# top_tnb_mns_control.net
KiCad netlist of a schematic drawn in Altium Designer
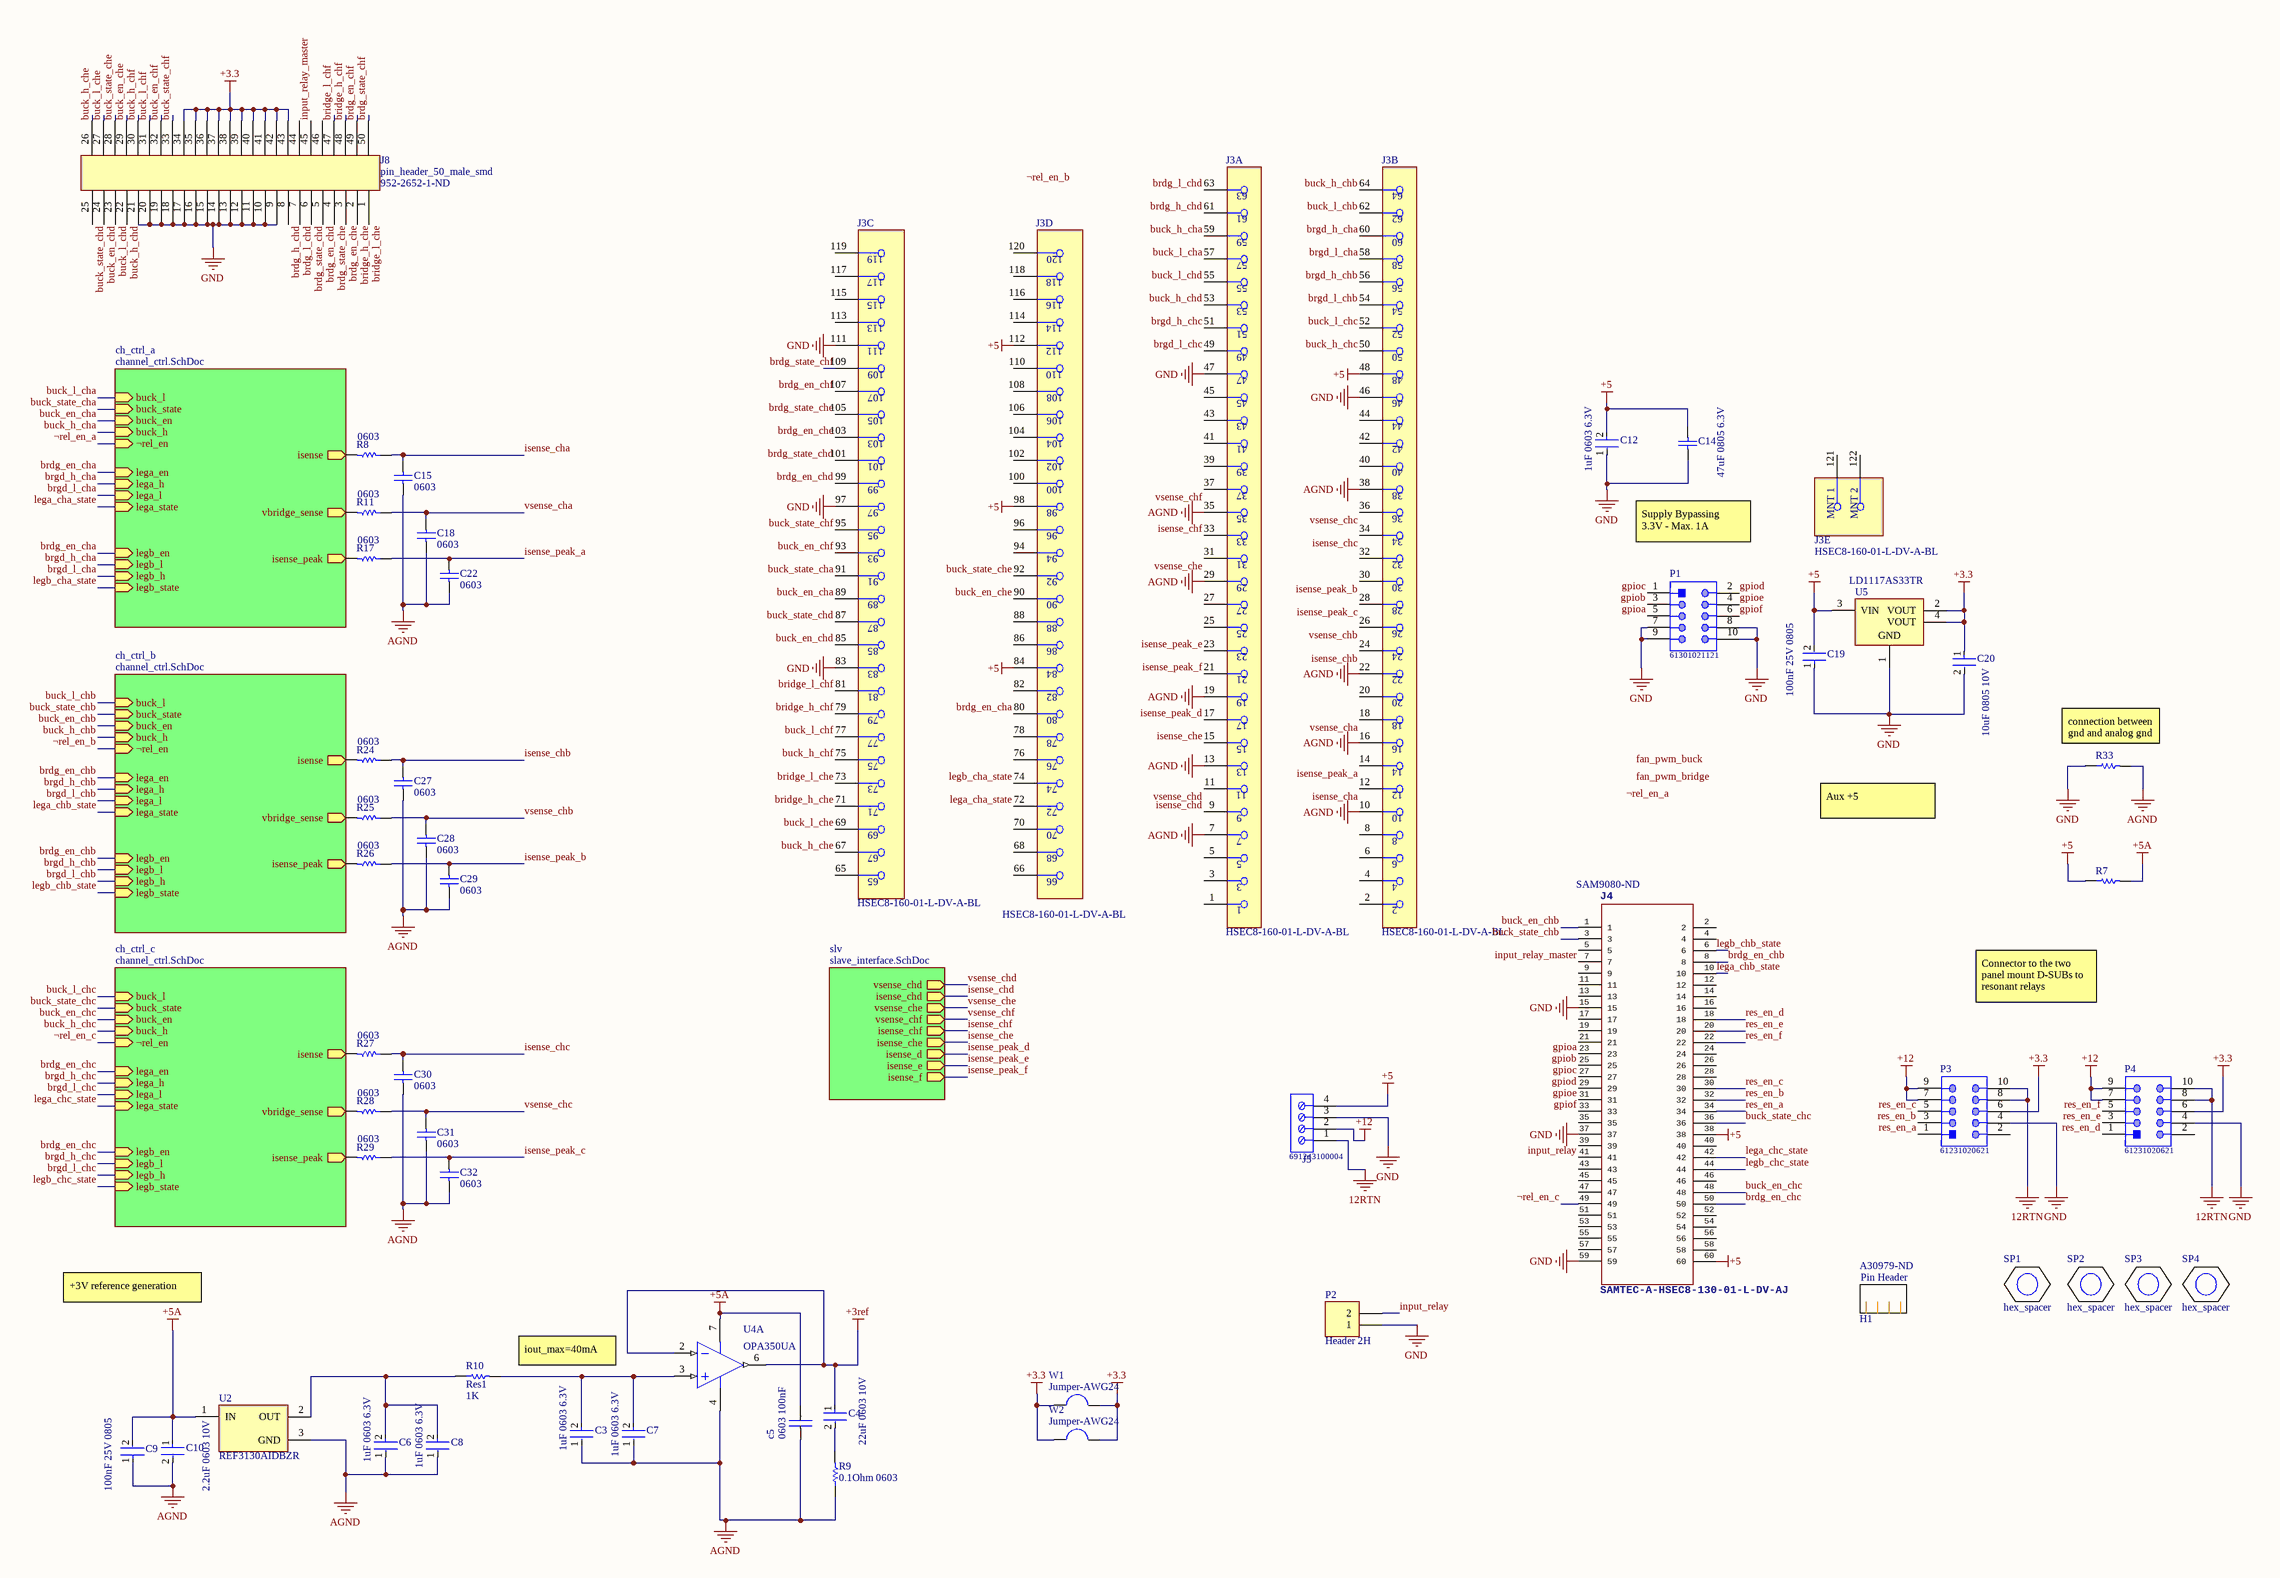
[diagram p0: top_tnb_mns_control.SchDoc]

(export (version "E")
  (design (tool "Eeschema 10.0.6"))
  (components
    (comp (ref "C3")
      (value "1uF 0603 6.3V")
      (footprint "FP-GRM188-0_1-MFG")
      (description "CAP CER 1UF 6.3V X5R 0603\r\nGRM188R60J105KA01D")
      (fields (field (name "TOLERANCE") "10%") (field (name "VOLTAGE") "6.3V"))
      (libsource (lib "Altium Content Vault") (part "236180d848d6139a670b325ea6854c9"))
    )
    (comp (ref "C4")
      (value "22uF 0603 10V")
      (footprint "FP-GRM188-0_2-IPC_C")
      (fields (field (name "TOLERANCE") "20%"))
      (libsource (lib "Altium Content Vault") (part "11868f565c42a9108669ba33697ecf6"))
    )
    (comp (ref "c5")
      (value "0603 100nF")
      (footprint "CAP 0603_1608")
      (libsource (lib "coil_driver_lib") (part "cap_smd"))
    )
    (comp (ref "C6")
      (value "1uF 0603 6.3V")
      (footprint "FP-GRM188-0_1-MFG")
      (description "CAP CER 1UF 6.3V X5R 0603\r\nGRM188R60J105KA01D")
      (fields (field (name "TOLERANCE") "10%") (field (name "VOLTAGE") "6.3V"))
      (libsource (lib "Altium Content Vault") (part "236180d848d6139a670b325ea6854c9"))
    )
    (comp (ref "C7")
      (value "1uF 0603 6.3V")
      (footprint "FP-GRM188-0_1-MFG")
      (description "CAP CER 1UF 6.3V X5R 0603\r\nGRM188R60J105KA01D")
      (fields (field (name "TOLERANCE") "10%") (field (name "VOLTAGE") "6.3V"))
      (libsource (lib "Altium Content Vault") (part "236180d848d6139a670b325ea6854c9"))
    )
    (comp (ref "C8")
      (value "1uF 0603 6.3V")
      (footprint "FP-GRM188-0_1-MFG")
      (description "CAP CER 1UF 6.3V X5R 0603\r\nGRM188R60J105KA01D")
      (fields (field (name "TOLERANCE") "10%") (field (name "VOLTAGE") "6.3V"))
      (libsource (lib "Altium Content Vault") (part "236180d848d6139a670b325ea6854c9"))
    )
    (comp (ref "C9")
      (value "100nF 25V 0805")
      (footprint "FP-CC0805-0_85-MFG")
      (description "CAP CER 0.1UF 25V X7R 0805")
      (fields (field (name "MANUFACTURER PART NUMBER") "CC0805KRX7R8BB104") (field (name "TOLERANCE") "0.1"))
      (libsource (lib "Altium Content Vault") (part "11868f565c42a9108669ba33697ecf6"))
    )
    (comp (ref "C10")
      (value "2.2uF 0603 10V")
      (footprint "FP-GRM188-0_1-e0_2_0_5-MFG")
      (fields (field (name "VOLTAGE") "10V") (field (name "TOLERANCE") "10%"))
      (libsource (lib "Altium Content Vault") (part "11868f565c42a9108669ba33697ecf6"))
    )
    (comp (ref "C12")
      (value "1uF 0603 6.3V")
      (footprint "FP-GRM188-0_1-MFG")
      (description "CAP CER 1UF 6.3V X5R 0603\r\nGRM188R60J105KA01D")
      (fields (field (name "TOLERANCE") "10%") (field (name "VOLTAGE") "6.3V"))
      (libsource (lib "Altium Content Vault") (part "236180d848d6139a670b325ea6854c9"))
    )
    (comp (ref "C14")
      (value "47uF 0805 6.3V")
      (footprint "CAPC2014X150X70LL20")
      (description "TACR476M006XTA")
      (fields (field (name "MANUFACTURER") "AVX Interconnect / Elco"))
      (libsource (lib "Altium Content Vault") (part "CAP"))
    )
    (comp (ref "C15")
      (value "0603")
      (footprint "CAP 0603_1608")
      (description "Capacitor")
      (fields (field (name "PUBLISHER") "Altium Limited"))
      (libsource (lib "Miscellaneous Devices") (part "Cap"))
    )
    (comp (ref "C18")
      (value "0603")
      (footprint "CAP 0603_1608")
      (description "Capacitor")
      (fields (field (name "PUBLISHER") "Altium Limited"))
      (libsource (lib "Miscellaneous Devices") (part "Cap"))
    )
    (comp (ref "C19")
      (value "100nF 25V 0805")
      (footprint "FP-CC0805-0_85-MFG")
      (description "CAP CER 0.1UF 25V X7R 0805")
      (fields (field (name "MANUFACTURER PART NUMBER") "CC0805KRX7R8BB104") (field (name "TOLERANCE") "0.1"))
      (libsource (lib "Altium Content Vault") (part "11868f565c42a9108669ba33697ecf6"))
    )
    (comp (ref "C20")
      (value "10uF 0805 10V")
      (footprint "FP-C0805C-DG-MFG")
      (description "CAP CER 10UF 10V X5R 0805\r\nC0805C106K8PACTU")
      (fields (field (name "TOLERANCE") "10%") (field (name "MANUFACTURER PART NUMBER") "C0805C106K8PACTU"))
      (libsource (lib "Altium Content Vault") (part "11868f565c42a9108669ba33697ecf6"))
    )
    (comp (ref "C22")
      (value "0603")
      (footprint "CAP 0603_1608")
      (description "Capacitor")
      (fields (field (name "PUBLISHER") "Altium Limited"))
      (libsource (lib "Miscellaneous Devices") (part "Cap"))
    )
    (comp (ref "C27")
      (value "0603")
      (footprint "CAP 0603_1608")
      (description "Capacitor")
      (fields (field (name "PUBLISHER") "Altium Limited"))
      (libsource (lib "Miscellaneous Devices") (part "Cap"))
    )
    (comp (ref "C28")
      (value "0603")
      (footprint "CAP 0603_1608")
      (description "Capacitor")
      (fields (field (name "PUBLISHER") "Altium Limited"))
      (libsource (lib "Miscellaneous Devices") (part "Cap"))
    )
    (comp (ref "C29")
      (value "0603")
      (footprint "CAP 0603_1608")
      (description "Capacitor")
      (fields (field (name "PUBLISHER") "Altium Limited"))
      (libsource (lib "Miscellaneous Devices") (part "Cap"))
    )
    (comp (ref "C30")
      (value "0603")
      (footprint "CAP 0603_1608")
      (description "Capacitor")
      (fields (field (name "PUBLISHER") "Altium Limited"))
      (libsource (lib "Miscellaneous Devices") (part "Cap"))
    )
    (comp (ref "C31")
      (value "0603")
      (footprint "CAP 0603_1608")
      (description "Capacitor")
      (fields (field (name "PUBLISHER") "Altium Limited"))
      (libsource (lib "Miscellaneous Devices") (part "Cap"))
    )
    (comp (ref "C32")
      (value "0603")
      (footprint "CAP 0603_1608")
      (description "Capacitor")
      (fields (field (name "PUBLISHER") "Altium Limited"))
      (libsource (lib "Miscellaneous Devices") (part "Cap"))
    )
    (comp (ref "H1")
      (value "Generic Pin  Header")
      (description "Assign Supplier Link Manually")
      (fields (field (name "SUPPLIER PART NUMBER 1") "A30979-ND"))
      (libsource (lib "coil_driver_lib") (part "generic_pin_header"))
    )
    (comp (ref "J3")
      (value "HSEC8-160-01-L-DV-A-BL")
      (footprint "FP-HSEC8-160-01-L-DV-A-BL-MFG")
      (description "CONN EDGE DUAL FMALE 120P 0.031")
      (libsource (lib "Altium Content Vault") (part "8744de41cb8216e3d623a7aa1f0e41a"))
    )
    (comp (ref "J4")
      (value "SAMTEC-A-HSEC8-130-01-L-DV-AJ")
      (footprint "SAMTEC-A-HSEC-120")
      (fields (field (name "SUPPLIER PART NUMBER 1") "SAM9080-ND"))
      (libsource (lib "SAMTEC-A-HSEC8-130-01-L-DV-A") (part "SAMTEC-A-HSEC8-130-01-L-DV-AJ"))
    )
    (comp (ref "J5")
      (value "691243100004")
      (footprint "691243100004")
      (description "Serie 2431- 3.50 mm Vertical Entry with Rising Cage Clamp WR-TBL, 4 pin")
      (fields (field (name "MANUFACTURER") "Wurth Elektronik") (field (name "PUBLISHER") "WurthElektronik"))
      (libsource (lib "Altium Content Vault") (part "WE-CN-1P-F-TB4"))
    )
    (comp (ref "J8")
      (value "pin_header_50_male_smd")
      (footprint "pin_connector_50_m_1.27_smd")
      (description "Mating Product : 952-2565-ND")
      (fields (field (name "SUPPLIER PART NUMBER 1") "952-2652-1-ND"))
      (libsource (lib "coil_driver_lib") (part "pin_header_50_male_smd"))
    )
    (comp (ref "P1")
      (value "61301021121")
      (footprint "61301021121")
      (description "THT Vertical Pin Header WR-PHD, Pitch 2.54 mm, Dual Row, 10 pins")
      (fields (field (name "MANUFACTURER") "Wurth Elektronik") (field (name "PUBLISHER") "WurthElektronik"))
      (libsource (lib "Altium Content Vault") (part "WE-CN-2P-M-R10"))
    )
    (comp (ref "P2")
      (value "Header 2H")
      (footprint "HEADER_1_2_f")
      (description "Header, 2-Pin, Right Angle")
      (fields (field (name "PUBLISHER") "Altium Limited"))
      (libsource (lib "Miscellaneous Connectors") (part "Header 2H"))
    )
    (comp (ref "P3")
      (value "61231020621")
      (footprint "61231020621")
      (description "Male Box Header WR-BHD, SMT, Vertical, pitch 2.54 mm, 10 pins")
      (fields (field (name "MANUFACTURER") "Wurth Elektronik") (field (name "PUBLISHER") "WurthElektronik"))
      (libsource (lib "") (part "WE-CN-2P-M-R10_1"))
    )
    (comp (ref "P4")
      (value "61231020621")
      (footprint "61231020621")
      (description "Male Box Header WR-BHD, SMT, Vertical, pitch 2.54 mm, 10 pins")
      (fields (field (name "MANUFACTURER") "Wurth Elektronik") (field (name "PUBLISHER") "WurthElektronik"))
      (libsource (lib "") (part "WE-CN-2P-M-R10_1"))
    )
    (comp (ref "R7")
      (value "0")
      (footprint "RES 0805_2012")
      (description "Resistor")
      (fields (field (name "PUBLISHER") "Altium Limited"))
      (libsource (lib "Miscellaneous Devices") (part "Res1"))
    )
    (comp (ref "R8")
      (value "0603")
      (footprint "RES 0603_1608")
      (description "Resistor")
      (fields (field (name "PUBLISHER") "Altium Limited"))
      (libsource (lib "Miscellaneous Devices") (part "Res1"))
    )
    (comp (ref "R9")
      (value "0.1Ohm 0603")
      (footprint "RESC1508X46X38NL25T25")
      (description "WSL0603R1000FEA")
      (fields (field (name "MANUFACTURER") "Vishay Dale"))
      (libsource (lib "Altium Content Vault") (part "RES"))
    )
    (comp (ref "R10")
      (value "Res1")
      (footprint "RES 0603_1608")
      (description "Resistor")
      (fields (field (name "ALTIUM_VALUE") "1K") (field (name "PUBLISHER") "Altium Limited"))
      (libsource (lib "Miscellaneous Devices") (part "Res1"))
    )
    (comp (ref "R11")
      (value "0603")
      (footprint "RES 0603_1608")
      (description "Resistor")
      (fields (field (name "PUBLISHER") "Altium Limited"))
      (libsource (lib "Miscellaneous Devices") (part "Res1"))
    )
    (comp (ref "R17")
      (value "0603")
      (footprint "RES 0603_1608")
      (description "Resistor")
      (fields (field (name "PUBLISHER") "Altium Limited"))
      (libsource (lib "Miscellaneous Devices") (part "Res1"))
    )
    (comp (ref "R24")
      (value "0603")
      (footprint "RES 0603_1608")
      (description "Resistor")
      (fields (field (name "PUBLISHER") "Altium Limited"))
      (libsource (lib "Miscellaneous Devices") (part "Res1"))
    )
    (comp (ref "R25")
      (value "0603")
      (footprint "RES 0603_1608")
      (description "Resistor")
      (fields (field (name "PUBLISHER") "Altium Limited"))
      (libsource (lib "Miscellaneous Devices") (part "Res1"))
    )
    (comp (ref "R26")
      (value "0603")
      (footprint "RES 0603_1608")
      (description "Resistor")
      (fields (field (name "PUBLISHER") "Altium Limited"))
      (libsource (lib "Miscellaneous Devices") (part "Res1"))
    )
    (comp (ref "R27")
      (value "0603")
      (footprint "RES 0603_1608")
      (description "Resistor")
      (fields (field (name "PUBLISHER") "Altium Limited"))
      (libsource (lib "Miscellaneous Devices") (part "Res1"))
    )
    (comp (ref "R28")
      (value "0603")
      (footprint "RES 0603_1608")
      (description "Resistor")
      (fields (field (name "PUBLISHER") "Altium Limited"))
      (libsource (lib "Miscellaneous Devices") (part "Res1"))
    )
    (comp (ref "R29")
      (value "0603")
      (footprint "RES 0603_1608")
      (description "Resistor")
      (fields (field (name "PUBLISHER") "Altium Limited"))
      (libsource (lib "Miscellaneous Devices") (part "Res1"))
    )
    (comp (ref "R33")
      (value "0")
      (footprint "RES 0805_2012")
      (description "Resistor")
      (fields (field (name "PUBLISHER") "Altium Limited"))
      (libsource (lib "Miscellaneous Devices") (part "Res1"))
    )
    (comp (ref "SP1")
      (value "hex_spacer")
      (footprint "HEX_SPACER_8MM_35MM")
      (libsource (lib "coil_driver_lib") (part "hex_spacer"))
    )
    (comp (ref "SP2")
      (value "hex_spacer")
      (footprint "HEX_SPACER_8MM_35MM")
      (libsource (lib "coil_driver_lib") (part "hex_spacer"))
    )
    (comp (ref "SP3")
      (value "hex_spacer")
      (footprint "HEX_SPACER_8MM_35MM")
      (libsource (lib "coil_driver_lib") (part "hex_spacer"))
    )
    (comp (ref "SP4")
      (value "hex_spacer")
      (footprint "HEX_SPACER_8MM_35MM")
      (libsource (lib "coil_driver_lib") (part "hex_spacer"))
    )
    (comp (ref "U2")
      (value "REF3130AIDBZR")
      (footprint "DBZ0003A_N")
      (fields (field (name "MANUFACTURER") "Texas Instruments"))
      (libsource (lib "Altium Content Vault") (part "TI-REF3130DBZ3"))
    )
    (comp (ref "U4")
      (value "OPA350UA")
      (footprint "D0008A_M")
      (fields (field (name "MANUFACTURER") "Texas Instruments"))
      (libsource (lib "Altium Content Vault") (part "TI-OPA-8_1"))
    )
    (comp (ref "U5")
      (value "LD1117AS33TR")
      (footprint "SOT-223_M")
      (description "1A, Low Drop Positive Voltage Regulator, 3.3V, 4-Pin SOT-223, Tape and Reel")
      (libsource (lib "Altium Content Vault") (part "PM-REG-LD1117-SOT4"))
    )
    (comp (ref "W1")
      (value "wire_jumper")
      (footprint "wire_jumper")
      (libsource (lib "coil_driver_lib") (part "wire_jumper"))
    )
    (comp (ref "W2")
      (value "wire_jumper")
      (footprint "wire_jumper")
      (libsource (lib "coil_driver_lib") (part "wire_jumper"))
    )
  )
  (nets
    (net (code "1") (name "+3.3") (class "Default")
      (node (ref "C20") (pin "1") (pinfunction "1_1") (pintype "passive"))
      (node (ref "J8") (pin "34") (pintype "passive"))
      (node (ref "J8") (pin "35") (pintype "passive"))
      (node (ref "J8") (pin "36") (pintype "passive"))
      (node (ref "J8") (pin "37") (pintype "passive"))
      (node (ref "J8") (pin "38") (pintype "passive"))
      (node (ref "J8") (pin "39") (pintype "passive"))
      (node (ref "J8") (pin "40") (pintype "passive"))
      (node (ref "J8") (pin "41") (pintype "passive"))
      (node (ref "J8") (pin "42") (pintype "passive"))
      (node (ref "J8") (pin "43") (pintype "passive"))
      (node (ref "P3") (pin "6") (pinfunction "6_6") (pintype "passive"))
      (node (ref "P4") (pin "6") (pinfunction "6_6") (pintype "passive"))
      (node (ref "U5") (pin "2") (pinfunction "VOUT_2") (pintype "power_in"))
      (node (ref "U5") (pin "4") (pinfunction "VOUT_4") (pintype "power_in"))
      (node (ref "W1") (pin "1") (pinfunction "1_1") (pintype "passive"))
      (node (ref "W1") (pin "2") (pinfunction "2_2") (pintype "passive"))
      (node (ref "W2") (pin "1") (pinfunction "1_1") (pintype "passive"))
      (node (ref "W2") (pin "2") (pinfunction "2_2") (pintype "passive"))
    )
    (net (code "2") (name "+3ref") (class "Default")
      (node (ref "C4") (pin "1") (pinfunction "1_1") (pintype "passive"))
      (node (ref "U4") (pin "2") (pinfunction "IN-_2") (pintype "input"))
      (node (ref "U4") (pin "6") (pinfunction "OUT_6") (pintype "output"))
    )
    (net (code "3") (name "+5") (class "Default")
      (node (ref "C12") (pin "2") (pinfunction "2_2") (pintype "passive"))
      (node (ref "C14") (pin "2") (pinfunction "2_2") (pintype "passive"))
      (node (ref "C19") (pin "2") (pinfunction "2_2") (pintype "passive"))
      (node (ref "J3") (pin "112") (pinfunction "112_112") (pintype "passive"))
      (node (ref "J3") (pin "48") (pinfunction "48_48") (pintype "passive"))
      (node (ref "J3") (pin "84") (pinfunction "84_84") (pintype "passive"))
      (node (ref "J3") (pin "98") (pinfunction "98_98") (pintype "passive"))
      (node (ref "J4") (pin "38") (pinfunction "38_38") (pintype "passive"))
      (node (ref "J4") (pin "60") (pinfunction "60_60") (pintype "passive"))
      (node (ref "J5") (pin "4") (pinfunction "4_4") (pintype "passive"))
      (node (ref "R7") (pin "1") (pinfunction "1_1") (pintype "passive"))
      (node (ref "U5") (pin "3") (pinfunction "VIN_3") (pintype "power_in"))
    )
    (net (code "4") (name "+5A") (class "Default")
      (node (ref "C10") (pin "1") (pinfunction "1_1") (pintype "passive"))
      (node (ref "C9") (pin "2") (pinfunction "2_2") (pintype "passive"))
      (node (ref "R7") (pin "2") (pinfunction "2_2") (pintype "passive"))
      (node (ref "U2") (pin "1") (pinfunction "IN_1") (pintype "power_in"))
      (node (ref "U4") (pin "7") (pinfunction "V+_7") (pintype "power_in"))
      (node (ref "c5") (pin "1") (pinfunction "1_1") (pintype "passive"))
    )
    (net (code "5") (name "+12") (class "Default")
      (node (ref "J5") (pin "2") (pinfunction "2_2") (pintype "passive"))
      (node (ref "P3") (pin "7") (pinfunction "7_7") (pintype "passive"))
      (node (ref "P3") (pin "9") (pinfunction "9_9") (pintype "passive"))
      (node (ref "P4") (pin "7") (pinfunction "7_7") (pintype "passive"))
      (node (ref "P4") (pin "9") (pinfunction "9_9") (pintype "passive"))
    )
    (net (code "6") (name "/brdg_en_cha") (class "Default")
      (node (ref "J3") (pin "80") (pinfunction "80_80") (pintype "passive"))
    )
    (net (code "7") (name "/brdg_en_chb") (class "Default")
      (node (ref "J4") (pin "8") (pinfunction "8_8") (pintype "passive"))
    )
    (net (code "8") (name "/brdg_en_chc") (class "Default")
      (node (ref "J4") (pin "50") (pinfunction "50_50") (pintype "passive"))
    )
    (net (code "9") (name "/brdg_en_chd") (class "Default")
      (node (ref "J3") (pin "99") (pinfunction "99_99") (pintype "passive"))
      (node (ref "J8") (pin "5") (pintype "passive"))
    )
    (net (code "10") (name "/brdg_en_che") (class "Default")
      (node (ref "J3") (pin "103") (pinfunction "103_103") (pintype "passive"))
      (node (ref "J8") (pin "3") (pintype "passive"))
    )
    (net (code "11") (name "/brdg_en_chf") (class "Default")
      (node (ref "J3") (pin "107") (pinfunction "107_107") (pintype "passive"))
      (node (ref "J8") (pin "49") (pintype "passive"))
    )
    (net (code "12") (name "/brdg_h_chd") (class "Default")
      (node (ref "J3") (pin "61") (pinfunction "61_61") (pintype "passive"))
      (node (ref "J8") (pin "8") (pintype "passive"))
    )
    (net (code "13") (name "/brdg_l_chd") (class "Default")
      (node (ref "J3") (pin "63") (pinfunction "63_63") (pintype "passive"))
      (node (ref "J8") (pin "7") (pintype "passive"))
    )
    (net (code "14") (name "/brdg_state_chd") (class "Default")
      (node (ref "J3") (pin "101") (pinfunction "101_101") (pintype "passive"))
      (node (ref "J8") (pin "6") (pintype "passive"))
    )
    (net (code "15") (name "/brdg_state_che") (class "Default")
      (node (ref "J3") (pin "105") (pinfunction "105_105") (pintype "passive"))
      (node (ref "J8") (pin "4") (pintype "passive"))
    )
    (net (code "16") (name "/brdg_state_chf") (class "Default")
      (node (ref "J3") (pin "109") (pinfunction "109_109") (pintype "passive"))
      (node (ref "J8") (pin "50") (pintype "passive"))
    )
    (net (code "17") (name "/brgd_h_cha") (class "Default")
      (node (ref "J3") (pin "60") (pinfunction "60_60") (pintype "passive"))
    )
    (net (code "18") (name "/brgd_h_chb") (class "Default")
      (node (ref "J3") (pin "56") (pinfunction "56_56") (pintype "passive"))
    )
    (net (code "19") (name "/brgd_h_chc") (class "Default")
      (node (ref "J3") (pin "51") (pinfunction "51_51") (pintype "passive"))
    )
    (net (code "20") (name "/brgd_l_cha") (class "Default")
      (node (ref "J3") (pin "58") (pinfunction "58_58") (pintype "passive"))
    )
    (net (code "21") (name "/brgd_l_chb") (class "Default")
      (node (ref "J3") (pin "54") (pinfunction "54_54") (pintype "passive"))
    )
    (net (code "22") (name "/brgd_l_chc") (class "Default")
      (node (ref "J3") (pin "49") (pinfunction "49_49") (pintype "passive"))
    )
    (net (code "23") (name "/bridge_h_che") (class "Default")
      (node (ref "J3") (pin "71") (pinfunction "71_71") (pintype "passive"))
      (node (ref "J8") (pin "2") (pintype "passive"))
    )
    (net (code "24") (name "/bridge_h_chf") (class "Default")
      (node (ref "J3") (pin "79") (pinfunction "79_79") (pintype "passive"))
      (node (ref "J8") (pin "48") (pintype "passive"))
    )
    (net (code "25") (name "/bridge_l_che") (class "Default")
      (node (ref "J3") (pin "73") (pinfunction "73_73") (pintype "passive"))
      (node (ref "J8") (pin "1") (pintype "passive"))
    )
    (net (code "26") (name "/bridge_l_chf") (class "Default")
      (node (ref "J3") (pin "81") (pinfunction "81_81") (pintype "passive"))
      (node (ref "J8") (pin "47") (pintype "passive"))
    )
    (net (code "27") (name "/buck_en_cha") (class "Default")
      (node (ref "J3") (pin "89") (pinfunction "89_89") (pintype "passive"))
    )
    (net (code "28") (name "/buck_en_chb") (class "Default")
      (node (ref "J4") (pin "1") (pinfunction "1_1") (pintype "passive"))
    )
    (net (code "29") (name "/buck_en_chc") (class "Default")
      (node (ref "J4") (pin "48") (pinfunction "48_48") (pintype "passive"))
    )
    (net (code "30") (name "/buck_en_chd") (class "Default")
      (node (ref "J3") (pin "85") (pinfunction "85_85") (pintype "passive"))
      (node (ref "J8") (pin "24") (pintype "passive"))
    )
    (net (code "31") (name "/buck_en_che") (class "Default")
      (node (ref "J3") (pin "90") (pinfunction "90_90") (pintype "passive"))
      (node (ref "J8") (pin "29") (pintype "passive"))
    )
    (net (code "32") (name "/buck_en_chf") (class "Default")
      (node (ref "J3") (pin "93") (pinfunction "93_93") (pintype "passive"))
      (node (ref "J8") (pin "32") (pintype "passive"))
    )
    (net (code "33") (name "/buck_h_cha") (class "Default")
      (node (ref "J3") (pin "59") (pinfunction "59_59") (pintype "passive"))
    )
    (net (code "34") (name "/buck_h_chb") (class "Default")
      (node (ref "J3") (pin "64") (pinfunction "64_64") (pintype "passive"))
    )
    (net (code "35") (name "/buck_h_chc") (class "Default")
      (node (ref "J3") (pin "50") (pinfunction "50_50") (pintype "passive"))
    )
    (net (code "36") (name "/buck_h_chd") (class "Default")
      (node (ref "J3") (pin "53") (pinfunction "53_53") (pintype "passive"))
      (node (ref "J8") (pin "22") (pintype "passive"))
    )
    (net (code "37") (name "/buck_h_che") (class "Default")
      (node (ref "J3") (pin "67") (pinfunction "67_67") (pintype "passive"))
      (node (ref "J8") (pin "26") (pintype "passive"))
    )
    (net (code "38") (name "/buck_h_chf") (class "Default")
      (node (ref "J3") (pin "75") (pinfunction "75_75") (pintype "passive"))
      (node (ref "J8") (pin "30") (pintype "passive"))
    )
    (net (code "39") (name "/buck_l_cha") (class "Default")
      (node (ref "J3") (pin "57") (pinfunction "57_57") (pintype "passive"))
    )
    (net (code "40") (name "/buck_l_chb") (class "Default")
      (node (ref "J3") (pin "62") (pinfunction "62_62") (pintype "passive"))
    )
    (net (code "41") (name "/buck_l_chc") (class "Default")
      (node (ref "J3") (pin "52") (pinfunction "52_52") (pintype "passive"))
    )
    (net (code "42") (name "/buck_l_chd") (class "Default")
      (node (ref "J3") (pin "55") (pinfunction "55_55") (pintype "passive"))
      (node (ref "J8") (pin "23") (pintype "passive"))
    )
    (net (code "43") (name "/buck_l_che") (class "Default")
      (node (ref "J3") (pin "69") (pinfunction "69_69") (pintype "passive"))
      (node (ref "J8") (pin "27") (pintype "passive"))
    )
    (net (code "44") (name "/buck_l_chf") (class "Default")
      (node (ref "J3") (pin "77") (pinfunction "77_77") (pintype "passive"))
      (node (ref "J8") (pin "31") (pintype "passive"))
    )
    (net (code "45") (name "/buck_state_cha") (class "Default")
      (node (ref "J3") (pin "91") (pinfunction "91_91") (pintype "passive"))
    )
    (net (code "46") (name "/buck_state_chb") (class "Default")
      (node (ref "J4") (pin "3") (pinfunction "3_3") (pintype "passive"))
    )
    (net (code "47") (name "/buck_state_chc") (class "Default")
      (node (ref "J4") (pin "36") (pinfunction "36_36") (pintype "passive"))
    )
    (net (code "48") (name "/buck_state_chd") (class "Default")
      (node (ref "J3") (pin "87") (pinfunction "87_87") (pintype "passive"))
      (node (ref "J8") (pin "25") (pintype "passive"))
    )
    (net (code "49") (name "/buck_state_che") (class "Default")
      (node (ref "J3") (pin "92") (pinfunction "92_92") (pintype "passive"))
      (node (ref "J8") (pin "28") (pintype "passive"))
    )
    (net (code "50") (name "/buck_state_chf") (class "Default")
      (node (ref "J3") (pin "95") (pinfunction "95_95") (pintype "passive"))
      (node (ref "J8") (pin "33") (pintype "passive"))
    )
    (net (code "53") (name "/gpioa") (class "Default")
      (node (ref "J4") (pin "23") (pinfunction "23_23") (pintype "passive"))
      (node (ref "P1") (pin "5") (pinfunction "5_5") (pintype "passive"))
    )
    (net (code "54") (name "/gpiob") (class "Default")
      (node (ref "J4") (pin "25") (pinfunction "25_25") (pintype "passive"))
      (node (ref "P1") (pin "3") (pinfunction "3_3") (pintype "passive"))
    )
    (net (code "55") (name "/gpioc") (class "Default")
      (node (ref "J4") (pin "27") (pinfunction "27_27") (pintype "passive"))
      (node (ref "P1") (pin "1") (pinfunction "1_1") (pintype "passive"))
    )
    (net (code "56") (name "/gpiod") (class "Default")
      (node (ref "J4") (pin "29") (pinfunction "29_29") (pintype "passive"))
      (node (ref "P1") (pin "2") (pinfunction "2_2") (pintype "passive"))
    )
    (net (code "57") (name "/gpioe") (class "Default")
      (node (ref "J4") (pin "31") (pinfunction "31_31") (pintype "passive"))
      (node (ref "P1") (pin "4") (pinfunction "4_4") (pintype "passive"))
    )
    (net (code "58") (name "/gpiof") (class "Default")
      (node (ref "J4") (pin "33") (pinfunction "33_33") (pintype "passive"))
      (node (ref "P1") (pin "6") (pinfunction "6_6") (pintype "passive"))
    )
    (net (code "59") (name "/input_relay") (class "Default")
      (node (ref "J4") (pin "41") (pinfunction "41_41") (pintype "passive"))
      (node (ref "P2") (pin "2") (pinfunction "2_2") (pintype "passive"))
    )
    (net (code "60") (name "/input_relay_master") (class "Default")
      (node (ref "J4") (pin "7") (pinfunction "7_7") (pintype "passive"))
      (node (ref "J8") (pin "45") (pintype "passive"))
    )
    (net (code "61") (name "/isense") (class "Default")
      (node (ref "R27") (pin "2") (pinfunction "2_2") (pintype "passive"))
    )
    (net (code "62") (name "/isense_1") (class "Default")
      (node (ref "R8") (pin "2") (pinfunction "2_2") (pintype "passive"))
    )
    (net (code "63") (name "/isense_2") (class "Default")
      (node (ref "R24") (pin "2") (pinfunction "2_2") (pintype "passive"))
    )
    (net (code "64") (name "/isense_cha") (class "Default")
      (node (ref "C15") (pin "2") (pinfunction "2_2") (pintype "passive"))
      (node (ref "J3") (pin "12") (pinfunction "12_12") (pintype "passive"))
      (node (ref "R8") (pin "1") (pinfunction "1_1") (pintype "passive"))
    )
    (net (code "65") (name "/isense_chb") (class "Default")
      (node (ref "C27") (pin "2") (pinfunction "2_2") (pintype "passive"))
      (node (ref "J3") (pin "24") (pinfunction "24_24") (pintype "passive"))
      (node (ref "R24") (pin "1") (pinfunction "1_1") (pintype "passive"))
    )
    (net (code "66") (name "/isense_chc") (class "Default")
      (node (ref "C30") (pin "2") (pinfunction "2_2") (pintype "passive"))
      (node (ref "J3") (pin "34") (pinfunction "34_34") (pintype "passive"))
      (node (ref "R27") (pin "1") (pinfunction "1_1") (pintype "passive"))
    )
    (net (code "67") (name "/isense_chd") (class "Default")
      (node (ref "J3") (pin "9") (pinfunction "9_9") (pintype "passive"))
    )
    (net (code "68") (name "/isense_che") (class "Default")
      (node (ref "J3") (pin "15") (pinfunction "15_15") (pintype "passive"))
    )
    (net (code "69") (name "/isense_chf") (class "Default")
      (node (ref "J3") (pin "33") (pinfunction "33_33") (pintype "passive"))
    )
    (net (code "70") (name "/isense_peak") (class "Default")
      (node (ref "R29") (pin "2") (pinfunction "2_2") (pintype "passive"))
    )
    (net (code "71") (name "/isense_peak_1") (class "Default")
      (node (ref "R17") (pin "2") (pinfunction "2_2") (pintype "passive"))
    )
    (net (code "72") (name "/isense_peak_2") (class "Default")
      (node (ref "R26") (pin "2") (pinfunction "2_2") (pintype "passive"))
    )
    (net (code "73") (name "/isense_peak_a") (class "Default")
      (node (ref "C22") (pin "2") (pinfunction "2_2") (pintype "passive"))
      (node (ref "J3") (pin "14") (pinfunction "14_14") (pintype "passive"))
      (node (ref "R17") (pin "1") (pinfunction "1_1") (pintype "passive"))
    )
    (net (code "74") (name "/isense_peak_b") (class "Default")
      (node (ref "C29") (pin "2") (pinfunction "2_2") (pintype "passive"))
      (node (ref "J3") (pin "30") (pinfunction "30_30") (pintype "passive"))
      (node (ref "R26") (pin "1") (pinfunction "1_1") (pintype "passive"))
    )
    (net (code "75") (name "/isense_peak_c") (class "Default")
      (node (ref "C32") (pin "2") (pinfunction "2_2") (pintype "passive"))
      (node (ref "J3") (pin "28") (pinfunction "28_28") (pintype "passive"))
      (node (ref "R29") (pin "1") (pinfunction "1_1") (pintype "passive"))
    )
    (net (code "76") (name "/isense_peak_d") (class "Default")
      (node (ref "J3") (pin "17") (pinfunction "17_17") (pintype "passive"))
    )
    (net (code "77") (name "/isense_peak_e") (class "Default")
      (node (ref "J3") (pin "23") (pinfunction "23_23") (pintype "passive"))
    )
    (net (code "78") (name "/isense_peak_f") (class "Default")
      (node (ref "J3") (pin "21") (pinfunction "21_21") (pintype "passive"))
    )
    (net (code "79") (name "/lega_cha_state") (class "Default")
      (node (ref "J3") (pin "72") (pinfunction "72_72") (pintype "passive"))
    )
    (net (code "80") (name "/lega_chb_state") (class "Default")
      (node (ref "J4") (pin "10") (pinfunction "10_10") (pintype "passive"))
    )
    (net (code "81") (name "/lega_chc_state") (class "Default")
      (node (ref "J4") (pin "42") (pinfunction "42_42") (pintype "passive"))
    )
    (net (code "82") (name "/legb_cha_state") (class "Default")
      (node (ref "J3") (pin "74") (pinfunction "74_74") (pintype "passive"))
    )
    (net (code "83") (name "/legb_chb_state") (class "Default")
      (node (ref "J4") (pin "6") (pinfunction "6_6") (pintype "passive"))
    )
    (net (code "84") (name "/legb_chc_state") (class "Default")
      (node (ref "J4") (pin "44") (pinfunction "44_44") (pintype "passive"))
    )
    (net (code "85") (name "/res_en_a") (class "Default")
      (node (ref "J4") (pin "34") (pinfunction "34_34") (pintype "passive"))
      (node (ref "P3") (pin "1") (pinfunction "1_1") (pintype "passive"))
    )
    (net (code "86") (name "/res_en_b") (class "Default")
      (node (ref "J4") (pin "32") (pinfunction "32_32") (pintype "passive"))
      (node (ref "P3") (pin "3") (pinfunction "3_3") (pintype "passive"))
    )
    (net (code "87") (name "/res_en_c") (class "Default")
      (node (ref "J4") (pin "30") (pinfunction "30_30") (pintype "passive"))
      (node (ref "P3") (pin "5") (pinfunction "5_5") (pintype "passive"))
    )
    (net (code "88") (name "/res_en_d") (class "Default")
      (node (ref "J4") (pin "18") (pinfunction "18_18") (pintype "passive"))
      (node (ref "P4") (pin "1") (pinfunction "1_1") (pintype "passive"))
    )
    (net (code "89") (name "/res_en_e") (class "Default")
      (node (ref "J4") (pin "20") (pinfunction "20_20") (pintype "passive"))
      (node (ref "P4") (pin "3") (pinfunction "3_3") (pintype "passive"))
    )
    (net (code "90") (name "/res_en_f") (class "Default")
      (node (ref "J4") (pin "22") (pinfunction "22_22") (pintype "passive"))
      (node (ref "P4") (pin "5") (pinfunction "5_5") (pintype "passive"))
    )
    (net (code "91") (name "/vbridge_sense") (class "Default")
      (node (ref "R28") (pin "2") (pinfunction "2_2") (pintype "passive"))
    )
    (net (code "92") (name "/vbridge_sense_1") (class "Default")
      (node (ref "R11") (pin "2") (pinfunction "2_2") (pintype "passive"))
    )
    (net (code "93") (name "/vbridge_sense_2") (class "Default")
      (node (ref "R25") (pin "2") (pinfunction "2_2") (pintype "passive"))
    )
    (net (code "94") (name "/vsense_cha") (class "Default")
      (node (ref "C18") (pin "2") (pinfunction "2_2") (pintype "passive"))
      (node (ref "J3") (pin "18") (pinfunction "18_18") (pintype "passive"))
      (node (ref "R11") (pin "1") (pinfunction "1_1") (pintype "passive"))
    )
    (net (code "95") (name "/vsense_chb") (class "Default")
      (node (ref "C28") (pin "2") (pinfunction "2_2") (pintype "passive"))
      (node (ref "J3") (pin "26") (pinfunction "26_26") (pintype "passive"))
      (node (ref "R25") (pin "1") (pinfunction "1_1") (pintype "passive"))
    )
    (net (code "96") (name "/vsense_chc") (class "Default")
      (node (ref "C31") (pin "2") (pinfunction "2_2") (pintype "passive"))
      (node (ref "J3") (pin "36") (pinfunction "36_36") (pintype "passive"))
      (node (ref "R28") (pin "1") (pinfunction "1_1") (pintype "passive"))
    )
    (net (code "97") (name "/vsense_chd") (class "Default")
      (node (ref "J3") (pin "11") (pinfunction "11_11") (pintype "passive"))
    )
    (net (code "98") (name "/vsense_che") (class "Default")
      (node (ref "J3") (pin "31") (pinfunction "31_31") (pintype "passive"))
    )
    (net (code "99") (name "/vsense_chf") (class "Default")
      (node (ref "J3") (pin "37") (pinfunction "37_37") (pintype "passive"))
    )
    (net (code "102") (name "/¬rel_en_c") (class "Default")
      (node (ref "J4") (pin "49") (pinfunction "49_49") (pintype "passive"))
    )
    (net (code "103") (name "12RTN") (class "Default")
      (node (ref "J5") (pin "1") (pinfunction "1_1") (pintype "passive"))
      (node (ref "P3") (pin "10") (pinfunction "10_10") (pintype "passive"))
      (node (ref "P3") (pin "8") (pinfunction "8_8") (pintype "passive"))
      (node (ref "P4") (pin "10") (pinfunction "10_10") (pintype "passive"))
      (node (ref "P4") (pin "8") (pinfunction "8_8") (pintype "passive"))
    )
    (net (code "104") (name "AGND") (class "Default")
      (node (ref "C10") (pin "2") (pinfunction "2_2") (pintype "passive"))
      (node (ref "C15") (pin "1") (pinfunction "1_1") (pintype "passive"))
      (node (ref "C18") (pin "1") (pinfunction "1_1") (pintype "passive"))
      (node (ref "C22") (pin "1") (pinfunction "1_1") (pintype "passive"))
      (node (ref "C27") (pin "1") (pinfunction "1_1") (pintype "passive"))
      (node (ref "C28") (pin "1") (pinfunction "1_1") (pintype "passive"))
      (node (ref "C29") (pin "1") (pinfunction "1_1") (pintype "passive"))
      (node (ref "C3") (pin "1") (pinfunction "1_1") (pintype "passive"))
      (node (ref "C30") (pin "1") (pinfunction "1_1") (pintype "passive"))
      (node (ref "C31") (pin "1") (pinfunction "1_1") (pintype "passive"))
      (node (ref "C32") (pin "1") (pinfunction "1_1") (pintype "passive"))
      (node (ref "C6") (pin "1") (pinfunction "1_1") (pintype "passive"))
      (node (ref "C7") (pin "1") (pinfunction "1_1") (pintype "passive"))
      (node (ref "C8") (pin "1") (pinfunction "1_1") (pintype "passive"))
      (node (ref "C9") (pin "1") (pinfunction "1_1") (pintype "passive"))
      (node (ref "J3") (pin "10") (pinfunction "10_10") (pintype "passive"))
      (node (ref "J3") (pin "13") (pinfunction "13_13") (pintype "passive"))
      (node (ref "J3") (pin "16") (pinfunction "16_16") (pintype "passive"))
      (node (ref "J3") (pin "19") (pinfunction "19_19") (pintype "passive"))
      (node (ref "J3") (pin "22") (pinfunction "22_22") (pintype "passive"))
      (node (ref "J3") (pin "29") (pinfunction "29_29") (pintype "passive"))
      (node (ref "J3") (pin "35") (pinfunction "35_35") (pintype "passive"))
      (node (ref "J3") (pin "38") (pinfunction "38_38") (pintype "passive"))
      (node (ref "J3") (pin "7") (pinfunction "7_7") (pintype "passive"))
      (node (ref "R33") (pin "2") (pinfunction "2_2") (pintype "passive"))
      (node (ref "R9") (pin "1") (pinfunction "1_1") (pintype "passive"))
      (node (ref "U2") (pin "3") (pinfunction "GND_3") (pintype "power_in"))
      (node (ref "U4") (pin "4") (pinfunction "V-_4") (pintype "power_in"))
      (node (ref "c5") (pin "2") (pinfunction "2_2") (pintype "passive"))
    )
    (net (code "105") (name "GND") (class "Default")
      (node (ref "C12") (pin "1") (pinfunction "1_1") (pintype "passive"))
      (node (ref "C14") (pin "1") (pinfunction "1_1") (pintype "passive"))
      (node (ref "C19") (pin "1") (pinfunction "1_1") (pintype "passive"))
      (node (ref "C20") (pin "2") (pinfunction "2_2") (pintype "passive"))
      (node (ref "J3") (pin "111") (pinfunction "111_111") (pintype "passive"))
      (node (ref "J3") (pin "46") (pinfunction "46_46") (pintype "passive"))
      (node (ref "J3") (pin "47") (pinfunction "47_47") (pintype "passive"))
      (node (ref "J3") (pin "83") (pinfunction "83_83") (pintype "passive"))
      (node (ref "J3") (pin "97") (pinfunction "97_97") (pintype "passive"))
      (node (ref "J4") (pin "15") (pinfunction "15_15") (pintype "passive"))
      (node (ref "J4") (pin "37") (pinfunction "37_37") (pintype "passive"))
      (node (ref "J4") (pin "59") (pinfunction "59_59") (pintype "passive"))
      (node (ref "J5") (pin "3") (pinfunction "3_3") (pintype "passive"))
      (node (ref "J8") (pin "10") (pintype "passive"))
      (node (ref "J8") (pin "11") (pintype "passive"))
      (node (ref "J8") (pin "12") (pintype "passive"))
      (node (ref "J8") (pin "13") (pintype "passive"))
      (node (ref "J8") (pin "14") (pintype "passive"))
      (node (ref "J8") (pin "15") (pintype "passive"))
      (node (ref "J8") (pin "16") (pintype "passive"))
      (node (ref "J8") (pin "17") (pintype "passive"))
      (node (ref "J8") (pin "18") (pintype "passive"))
      (node (ref "J8") (pin "19") (pintype "passive"))
      (node (ref "J8") (pin "20") (pintype "passive"))
      (node (ref "J8") (pin "21") (pintype "passive"))
      (node (ref "J8") (pin "9") (pintype "passive"))
      (node (ref "P1") (pin "10") (pinfunction "10_10") (pintype "passive"))
      (node (ref "P1") (pin "7") (pinfunction "7_7") (pintype "passive"))
      (node (ref "P1") (pin "8") (pinfunction "8_8") (pintype "passive"))
      (node (ref "P1") (pin "9") (pinfunction "9_9") (pintype "passive"))
      (node (ref "P2") (pin "1") (pinfunction "1_1") (pintype "passive"))
      (node (ref "P3") (pin "4") (pinfunction "4_4") (pintype "passive"))
      (node (ref "P4") (pin "4") (pinfunction "4_4") (pintype "passive"))
      (node (ref "R33") (pin "1") (pinfunction "1_1") (pintype "passive"))
      (node (ref "U5") (pin "1") (pinfunction "GND_1") (pintype "power_in"))
    )
    (net (code "106") (name "Net-(C4-Pad2)") (class "Default")
      (node (ref "C4") (pin "2") (pinfunction "2_2") (pintype "passive"))
      (node (ref "R9") (pin "2") (pinfunction "2_2") (pintype "passive"))
    )
    (net (code "107") (name "Net-(U2-OUT)") (class "Default")
      (node (ref "C6") (pin "2") (pinfunction "2_2") (pintype "passive"))
      (node (ref "C8") (pin "2") (pinfunction "2_2") (pintype "passive"))
      (node (ref "R10") (pin "1") (pinfunction "1_1") (pintype "passive"))
      (node (ref "U2") (pin "2") (pinfunction "OUT_2") (pintype "power_in"))
    )
    (net (code "108") (name "Net-(U4A-IN+)") (class "Default")
      (node (ref "C3") (pin "2") (pinfunction "2_2") (pintype "passive"))
      (node (ref "C7") (pin "2") (pinfunction "2_2") (pintype "passive"))
      (node (ref "R10") (pin "2") (pinfunction "2_2") (pintype "passive"))
      (node (ref "U4") (pin "3") (pinfunction "IN+_3") (pintype "input"))
    )
    (net (code "109") (name "unconnected-(J3-Pad1)") (class "Default")
      (node (ref "J3") (pin "1") (pinfunction "1_1") (pintype "passive"))
    )
    (net (code "110") (name "unconnected-(J3-Pad2)") (class "Default")
      (node (ref "J3") (pin "2") (pinfunction "2_2") (pintype "passive"))
    )
    (net (code "111") (name "unconnected-(J3-Pad3)") (class "Default")
      (node (ref "J3") (pin "3") (pinfunction "3_3") (pintype "passive"))
    )
    (net (code "112") (name "unconnected-(J3-Pad4)") (class "Default")
      (node (ref "J3") (pin "4") (pinfunction "4_4") (pintype "passive"))
    )
    (net (code "113") (name "unconnected-(J3-Pad5)") (class "Default")
      (node (ref "J3") (pin "5") (pinfunction "5_5") (pintype "passive"))
    )
    (net (code "114") (name "unconnected-(J3-Pad6)") (class "Default")
      (node (ref "J3") (pin "6") (pinfunction "6_6") (pintype "passive"))
    )
    (net (code "115") (name "unconnected-(J3-Pad8)") (class "Default")
      (node (ref "J3") (pin "8") (pinfunction "8_8") (pintype "passive"))
    )
    (net (code "116") (name "unconnected-(J3-Pad20)") (class "Default")
      (node (ref "J3") (pin "20") (pinfunction "20_20") (pintype "passive"))
    )
    (net (code "117") (name "unconnected-(J3-Pad25)") (class "Default")
      (node (ref "J3") (pin "25") (pinfunction "25_25") (pintype "passive"))
    )
    (net (code "118") (name "unconnected-(J3-Pad27)") (class "Default")
      (node (ref "J3") (pin "27") (pinfunction "27_27") (pintype "passive"))
    )
    (net (code "119") (name "unconnected-(J3-Pad32)") (class "Default")
      (node (ref "J3") (pin "32") (pinfunction "32_32") (pintype "passive"))
    )
    (net (code "120") (name "unconnected-(J3-Pad39)") (class "Default")
      (node (ref "J3") (pin "39") (pinfunction "39_39") (pintype "passive"))
    )
    (net (code "121") (name "unconnected-(J3-Pad40)") (class "Default")
      (node (ref "J3") (pin "40") (pinfunction "40_40") (pintype "passive"))
    )
    (net (code "122") (name "unconnected-(J3-Pad41)") (class "Default")
      (node (ref "J3") (pin "41") (pinfunction "41_41") (pintype "passive"))
    )
    (net (code "123") (name "unconnected-(J3-Pad42)") (class "Default")
      (node (ref "J3") (pin "42") (pinfunction "42_42") (pintype "passive"))
    )
    (net (code "124") (name "unconnected-(J3-Pad43)") (class "Default")
      (node (ref "J3") (pin "43") (pinfunction "43_43") (pintype "passive"))
    )
    (net (code "125") (name "unconnected-(J3-Pad44)") (class "Default")
      (node (ref "J3") (pin "44") (pinfunction "44_44") (pintype "passive"))
    )
    (net (code "126") (name "unconnected-(J3-Pad45)") (class "Default")
      (node (ref "J3") (pin "45") (pinfunction "45_45") (pintype "passive"))
    )
    (net (code "127") (name "unconnected-(J3-Pad65)") (class "Default")
      (node (ref "J3") (pin "65") (pinfunction "65_65") (pintype "passive"))
    )
    (net (code "128") (name "unconnected-(J3-Pad66)") (class "Default")
      (node (ref "J3") (pin "66") (pinfunction "66_66") (pintype "passive"))
    )
    (net (code "129") (name "unconnected-(J3-Pad68)") (class "Default")
      (node (ref "J3") (pin "68") (pinfunction "68_68") (pintype "passive"))
    )
    (net (code "130") (name "unconnected-(J3-Pad70)") (class "Default")
      (node (ref "J3") (pin "70") (pinfunction "70_70") (pintype "passive"))
    )
    (net (code "131") (name "unconnected-(J3-Pad76)") (class "Default")
      (node (ref "J3") (pin "76") (pinfunction "76_76") (pintype "passive"))
    )
    (net (code "132") (name "unconnected-(J3-Pad78)") (class "Default")
      (node (ref "J3") (pin "78") (pinfunction "78_78") (pintype "passive"))
    )
    (net (code "133") (name "unconnected-(J3-Pad82)") (class "Default")
      (node (ref "J3") (pin "82") (pinfunction "82_82") (pintype "passive"))
    )
    (net (code "134") (name "unconnected-(J3-Pad86)") (class "Default")
      (node (ref "J3") (pin "86") (pinfunction "86_86") (pintype "passive"))
    )
    (net (code "135") (name "unconnected-(J3-Pad88)") (class "Default")
      (node (ref "J3") (pin "88") (pinfunction "88_88") (pintype "passive"))
    )
    (net (code "136") (name "unconnected-(J3-Pad94)") (class "Default")
      (node (ref "J3") (pin "94") (pinfunction "94_94") (pintype "passive"))
    )
    (net (code "137") (name "unconnected-(J3-Pad96)") (class "Default")
      (node (ref "J3") (pin "96") (pinfunction "96_96") (pintype "passive"))
    )
    (net (code "138") (name "unconnected-(J3-Pad100)") (class "Default")
      (node (ref "J3") (pin "100") (pinfunction "100_100") (pintype "passive"))
    )
    (net (code "139") (name "unconnected-(J3-Pad102)") (class "Default")
      (node (ref "J3") (pin "102") (pinfunction "102_102") (pintype "passive"))
    )
    (net (code "140") (name "unconnected-(J3-Pad104)") (class "Default")
      (node (ref "J3") (pin "104") (pinfunction "104_104") (pintype "passive"))
    )
    (net (code "141") (name "unconnected-(J3-Pad106)") (class "Default")
      (node (ref "J3") (pin "106") (pinfunction "106_106") (pintype "passive"))
    )
    (net (code "142") (name "unconnected-(J3-Pad108)") (class "Default")
      (node (ref "J3") (pin "108") (pinfunction "108_108") (pintype "passive"))
    )
    (net (code "143") (name "unconnected-(J3-Pad110)") (class "Default")
      (node (ref "J3") (pin "110") (pinfunction "110_110") (pintype "passive"))
    )
    (net (code "144") (name "unconnected-(J3-Pad113)") (class "Default")
      (node (ref "J3") (pin "113") (pinfunction "113_113") (pintype "passive"))
    )
    (net (code "145") (name "unconnected-(J3-Pad114)") (class "Default")
      (node (ref "J3") (pin "114") (pinfunction "114_114") (pintype "passive"))
    )
    (net (code "146") (name "unconnected-(J3-Pad115)") (class "Default")
      (node (ref "J3") (pin "115") (pinfunction "115_115") (pintype "passive"))
    )
    (net (code "147") (name "unconnected-(J3-Pad116)") (class "Default")
      (node (ref "J3") (pin "116") (pinfunction "116_116") (pintype "passive"))
    )
    (net (code "148") (name "unconnected-(J3-Pad117)") (class "Default")
      (node (ref "J3") (pin "117") (pinfunction "117_117") (pintype "passive"))
    )
    (net (code "149") (name "unconnected-(J3-Pad118)") (class "Default")
      (node (ref "J3") (pin "118") (pinfunction "118_118") (pintype "passive"))
    )
    (net (code "150") (name "unconnected-(J3-Pad119)") (class "Default")
      (node (ref "J3") (pin "119") (pinfunction "119_119") (pintype "passive"))
    )
    (net (code "151") (name "unconnected-(J3-Pad120)") (class "Default")
      (node (ref "J3") (pin "120") (pinfunction "120_120") (pintype "passive"))
    )
    (net (code "152") (name "unconnected-(J3E-MNT_1-Pad121)") (class "Default")
      (node (ref "J3") (pin "121") (pinfunction "MNT_1_121") (pintype "passive"))
    )
    (net (code "153") (name "unconnected-(J3E-MNT_2-Pad122)") (class "Default")
      (node (ref "J3") (pin "122") (pinfunction "MNT_2_122") (pintype "passive"))
    )
    (net (code "154") (name "unconnected-(J4-Pad2)") (class "Default")
      (node (ref "J4") (pin "2") (pinfunction "2_2") (pintype "passive"))
    )
    (net (code "155") (name "unconnected-(J4-Pad4)") (class "Default")
      (node (ref "J4") (pin "4") (pinfunction "4_4") (pintype "passive"))
    )
    (net (code "156") (name "unconnected-(J4-Pad5)") (class "Default")
      (node (ref "J4") (pin "5") (pinfunction "5_5") (pintype "passive"))
    )
    (net (code "157") (name "unconnected-(J4-Pad9)") (class "Default")
      (node (ref "J4") (pin "9") (pinfunction "9_9") (pintype "passive"))
    )
    (net (code "158") (name "unconnected-(J4-Pad11)") (class "Default")
      (node (ref "J4") (pin "11") (pinfunction "11_11") (pintype "passive"))
    )
    (net (code "159") (name "unconnected-(J4-Pad12)") (class "Default")
      (node (ref "J4") (pin "12") (pinfunction "12_12") (pintype "passive"))
    )
    (net (code "160") (name "unconnected-(J4-Pad13)") (class "Default")
      (node (ref "J4") (pin "13") (pinfunction "13_13") (pintype "passive"))
    )
    (net (code "161") (name "unconnected-(J4-Pad14)") (class "Default")
      (node (ref "J4") (pin "14") (pinfunction "14_14") (pintype "passive"))
    )
    (net (code "162") (name "unconnected-(J4-Pad16)") (class "Default")
      (node (ref "J4") (pin "16") (pinfunction "16_16") (pintype "passive"))
    )
    (net (code "163") (name "unconnected-(J4-Pad17)") (class "Default")
      (node (ref "J4") (pin "17") (pinfunction "17_17") (pintype "passive"))
    )
    (net (code "164") (name "unconnected-(J4-Pad19)") (class "Default")
      (node (ref "J4") (pin "19") (pinfunction "19_19") (pintype "passive"))
    )
    (net (code "165") (name "unconnected-(J4-Pad21)") (class "Default")
      (node (ref "J4") (pin "21") (pinfunction "21_21") (pintype "passive"))
    )
    (net (code "166") (name "unconnected-(J4-Pad24)") (class "Default")
      (node (ref "J4") (pin "24") (pinfunction "24_24") (pintype "passive"))
    )
    (net (code "167") (name "unconnected-(J4-Pad26)") (class "Default")
      (node (ref "J4") (pin "26") (pinfunction "26_26") (pintype "passive"))
    )
    (net (code "168") (name "unconnected-(J4-Pad28)") (class "Default")
      (node (ref "J4") (pin "28") (pinfunction "28_28") (pintype "passive"))
    )
    (net (code "169") (name "unconnected-(J4-Pad35)") (class "Default")
      (node (ref "J4") (pin "35") (pinfunction "35_35") (pintype "passive"))
    )
    (net (code "170") (name "unconnected-(J4-Pad39)") (class "Default")
      (node (ref "J4") (pin "39") (pinfunction "39_39") (pintype "passive"))
    )
    (net (code "171") (name "unconnected-(J4-Pad40)") (class "Default")
      (node (ref "J4") (pin "40") (pinfunction "40_40") (pintype "passive"))
    )
    (net (code "172") (name "unconnected-(J4-Pad43)") (class "Default")
      (node (ref "J4") (pin "43") (pinfunction "43_43") (pintype "passive"))
    )
    (net (code "173") (name "unconnected-(J4-Pad45)") (class "Default")
      (node (ref "J4") (pin "45") (pinfunction "45_45") (pintype "passive"))
    )
    (net (code "174") (name "unconnected-(J4-Pad46)") (class "Default")
      (node (ref "J4") (pin "46") (pinfunction "46_46") (pintype "passive"))
    )
    (net (code "175") (name "unconnected-(J4-Pad47)") (class "Default")
      (node (ref "J4") (pin "47") (pinfunction "47_47") (pintype "passive"))
    )
    (net (code "176") (name "unconnected-(J4-Pad51)") (class "Default")
      (node (ref "J4") (pin "51") (pinfunction "51_51") (pintype "passive"))
    )
    (net (code "177") (name "unconnected-(J4-Pad52)") (class "Default")
      (node (ref "J4") (pin "52") (pinfunction "52_52") (pintype "passive"))
    )
    (net (code "178") (name "unconnected-(J4-Pad53)") (class "Default")
      (node (ref "J4") (pin "53") (pinfunction "53_53") (pintype "passive"))
    )
    (net (code "179") (name "unconnected-(J4-Pad54)") (class "Default")
      (node (ref "J4") (pin "54") (pinfunction "54_54") (pintype "passive"))
    )
    (net (code "180") (name "unconnected-(J4-Pad55)") (class "Default")
      (node (ref "J4") (pin "55") (pinfunction "55_55") (pintype "passive"))
    )
    (net (code "181") (name "unconnected-(J4-Pad56)") (class "Default")
      (node (ref "J4") (pin "56") (pinfunction "56_56") (pintype "passive"))
    )
    (net (code "182") (name "unconnected-(J4-Pad57)") (class "Default")
      (node (ref "J4") (pin "57") (pinfunction "57_57") (pintype "passive"))
    )
    (net (code "183") (name "unconnected-(J4-Pad58)") (class "Default")
      (node (ref "J4") (pin "58") (pinfunction "58_58") (pintype "passive"))
    )
    (net (code "184") (name "unconnected-(J8-Pad44)") (class "Default")
      (node (ref "J8") (pin "44") (pintype "passive"))
    )
    (net (code "185") (name "unconnected-(J8-Pad46)") (class "Default")
      (node (ref "J8") (pin "46") (pintype "passive"))
    )
    (net (code "186") (name "unconnected-(P3-Pad2)") (class "Default")
      (node (ref "P3") (pin "2") (pinfunction "2_2") (pintype "passive"))
    )
    (net (code "187") (name "unconnected-(P4-Pad2)") (class "Default")
      (node (ref "P4") (pin "2") (pinfunction "2_2") (pintype "passive"))
    )
  )
)
